# Proximity_Sensors.net
KiCad netlist of a schematic drawn in Altium Designer
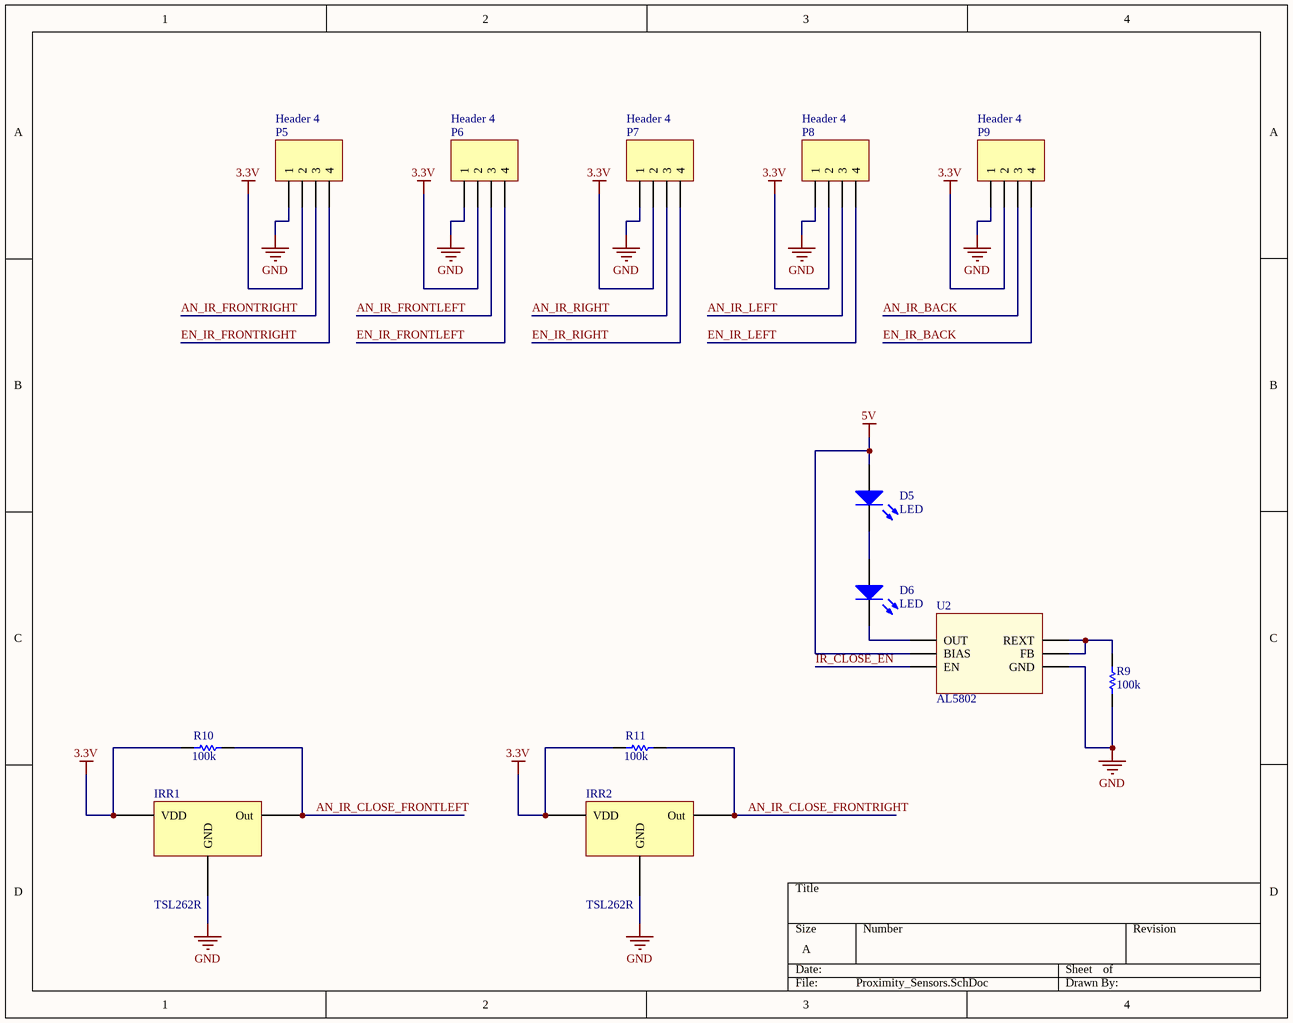
[diagram p0: Proximity_Sensors.SchDoc]

(export (version "E")
  (design (tool "Eeschema 10.0.6"))
  (components
    (comp (ref "D5")
      (value "LED")
      (footprint "LED-Bent")
      (fields
        (field (name "VENDOR PART NUMBER") "751-1203-ND")
        (field (name "MANUFACTURER") "Vishay")
        (field (name "MANUFACTURER PART NUMBER") "TSAL6100")
        (field (name "PUBLISHER") "Anthony Merlino")
      )
      (libsource (lib "passives") (part "LED"))
    )
    (comp (ref "D6")
      (value "LED")
      (footprint "LED-Bent")
      (fields
        (field (name "VENDOR PART NUMBER") "751-1203-ND")
        (field (name "MANUFACTURER") "Vishay")
        (field (name "MANUFACTURER PART NUMBER") "TSAL6100")
        (field (name "PUBLISHER") "Anthony Merlino")
      )
      (libsource (lib "passives") (part "LED"))
    )
    (comp (ref "IRR1") (value "TSL262R") (footprint "TSL262R") (libsource (lib "Devices") (part "TSL262R")))
    (comp (ref "IRR2") (value "TSL262R") (footprint "TSL262R") (libsource (lib "Devices") (part "TSL262R")))
    (comp (ref "P5")
      (value "Header 4")
      (footprint "HDR1X4")
      (description "Header, 4-Pin")
      (fields (field (name "PUBLISHER") "Altium Limited"))
      (libsource (lib "Miscellaneous Connectors") (part "Header 4"))
    )
    (comp (ref "P6")
      (value "Header 4")
      (footprint "HDR1X4")
      (description "Header, 4-Pin")
      (fields (field (name "PUBLISHER") "Altium Limited"))
      (libsource (lib "Miscellaneous Connectors") (part "Header 4"))
    )
    (comp (ref "P7")
      (value "Header 4")
      (footprint "HDR1X4")
      (description "Header, 4-Pin")
      (fields (field (name "PUBLISHER") "Altium Limited"))
      (libsource (lib "Miscellaneous Connectors") (part "Header 4"))
    )
    (comp (ref "P8")
      (value "Header 4")
      (footprint "HDR1X4")
      (description "Header, 4-Pin")
      (fields (field (name "PUBLISHER") "Altium Limited"))
      (libsource (lib "Miscellaneous Connectors") (part "Header 4"))
    )
    (comp (ref "P9")
      (value "Header 4")
      (footprint "HDR1X4")
      (description "Header, 4-Pin")
      (fields (field (name "PUBLISHER") "Altium Limited"))
      (libsource (lib "Miscellaneous Connectors") (part "Header 4"))
    )
    (comp (ref "R9")
      (value "100k")
      (footprint "0805")
      (description "Resistor")
      (fields (field (name "PUBLISHER") "Altium Limited"))
      (libsource (lib "passives") (part "Resistor"))
    )
    (comp (ref "R10")
      (value "100k")
      (footprint "0805")
      (description "Resistor")
      (fields (field (name "PUBLISHER") "Altium Limited"))
      (libsource (lib "passives") (part "Resistor"))
    )
    (comp (ref "R11")
      (value "100k")
      (footprint "0805")
      (description "Resistor")
      (fields (field (name "PUBLISHER") "Altium Limited"))
      (libsource (lib "passives") (part "Resistor"))
    )
    (comp (ref "U2") (value "AL5802") (footprint "SOT26") (libsource (lib "Devices") (part "AL5802")))
  )
  (nets
    (net (code "1") (name "/AN_IR_BACK") (class "Default")
      (node (ref "P9") (pin "3") (pinfunction "3_3") (pintype "passive"))
    )
    (net (code "2") (name "/AN_IR_CLOSE_FRONTLEFT") (class "Default")
      (node (ref "IRR1") (pin "2") (pinfunction "Out_2") (pintype "passive"))
      (node (ref "R10") (pin "2") (pinfunction "2_2") (pintype "passive"))
    )
    (net (code "3") (name "/AN_IR_CLOSE_FRONTRIGHT") (class "Default")
      (node (ref "IRR2") (pin "2") (pinfunction "Out_2") (pintype "passive"))
      (node (ref "R11") (pin "2") (pinfunction "2_2") (pintype "passive"))
    )
    (net (code "4") (name "/AN_IR_FRONTLEFT") (class "Default")
      (node (ref "P6") (pin "3") (pinfunction "3_3") (pintype "passive"))
    )
    (net (code "5") (name "/AN_IR_FRONTRIGHT") (class "Default")
      (node (ref "P5") (pin "3") (pinfunction "3_3") (pintype "passive"))
    )
    (net (code "6") (name "/AN_IR_LEFT") (class "Default")
      (node (ref "P8") (pin "3") (pinfunction "3_3") (pintype "passive"))
    )
    (net (code "7") (name "/AN_IR_RIGHT") (class "Default")
      (node (ref "P7") (pin "3") (pinfunction "3_3") (pintype "passive"))
    )
    (net (code "8") (name "/EN_IR_BACK") (class "Default")
      (node (ref "P9") (pin "4") (pinfunction "4_4") (pintype "passive"))
    )
    (net (code "9") (name "/EN_IR_FRONTLEFT") (class "Default")
      (node (ref "P6") (pin "4") (pinfunction "4_4") (pintype "passive"))
    )
    (net (code "10") (name "/EN_IR_FRONTRIGHT") (class "Default")
      (node (ref "P5") (pin "4") (pinfunction "4_4") (pintype "passive"))
    )
    (net (code "11") (name "/EN_IR_LEFT") (class "Default")
      (node (ref "P8") (pin "4") (pinfunction "4_4") (pintype "passive"))
    )
    (net (code "12") (name "/EN_IR_RIGHT") (class "Default")
      (node (ref "P7") (pin "4") (pinfunction "4_4") (pintype "passive"))
    )
    (net (code "13") (name "/IR_CLOSE_EN") (class "Default")
      (node (ref "U2") (pin "3") (pinfunction "EN_3") (pintype "passive"))
    )
    (net (code "14") (name "3.3V") (class "Default")
      (node (ref "IRR1") (pin "1") (pinfunction "VDD_1") (pintype "passive"))
      (node (ref "IRR2") (pin "1") (pinfunction "VDD_1") (pintype "passive"))
      (node (ref "P5") (pin "2") (pinfunction "2_2") (pintype "passive"))
      (node (ref "P6") (pin "2") (pinfunction "2_2") (pintype "passive"))
      (node (ref "P7") (pin "2") (pinfunction "2_2") (pintype "passive"))
      (node (ref "P8") (pin "2") (pinfunction "2_2") (pintype "passive"))
      (node (ref "P9") (pin "2") (pinfunction "2_2") (pintype "passive"))
      (node (ref "R10") (pin "1") (pinfunction "1_1") (pintype "passive"))
      (node (ref "R11") (pin "1") (pinfunction "1_1") (pintype "passive"))
    )
    (net (code "15") (name "5V") (class "Default")
      (node (ref "D5") (pin "1") (pinfunction "A_1") (pintype "passive"))
      (node (ref "U2") (pin "2") (pinfunction "BIAS_2") (pintype "passive"))
    )
    (net (code "16") (name "GND") (class "Default")
      (node (ref "IRR1") (pin "0") (pinfunction "GND_0") (pintype "passive"))
      (node (ref "IRR2") (pin "0") (pinfunction "GND_0") (pintype "passive"))
      (node (ref "P5") (pin "1") (pinfunction "1_1") (pintype "passive"))
      (node (ref "P6") (pin "1") (pinfunction "1_1") (pintype "passive"))
      (node (ref "P7") (pin "1") (pinfunction "1_1") (pintype "passive"))
      (node (ref "P8") (pin "1") (pinfunction "1_1") (pintype "passive"))
      (node (ref "P9") (pin "1") (pinfunction "1_1") (pintype "passive"))
      (node (ref "R9") (pin "1") (pinfunction "1_1") (pintype "passive"))
      (node (ref "U2") (pin "4") (pinfunction "GND_4") (pintype "passive"))
    )
    (net (code "17") (name "Net-(D5-K)") (class "Default")
      (node (ref "D5") (pin "2") (pinfunction "K_2") (pintype "passive"))
      (node (ref "D6") (pin "1") (pinfunction "A_1") (pintype "passive"))
    )
    (net (code "18") (name "Net-(D6-K)") (class "Default")
      (node (ref "D6") (pin "2") (pinfunction "K_2") (pintype "passive"))
      (node (ref "U2") (pin "1") (pinfunction "OUT_1") (pintype "passive"))
    )
    (net (code "19") (name "Net-(U2-FB)") (class "Default")
      (node (ref "R9") (pin "2") (pinfunction "2_2") (pintype "passive"))
      (node (ref "U2") (pin "5") (pinfunction "FB_5") (pintype "passive"))
      (node (ref "U2") (pin "6") (pinfunction "REXT_6") (pintype "passive"))
    )
  )
)
